# Audio_Amp.net
KiCad netlist of a schematic drawn in Altium Designer
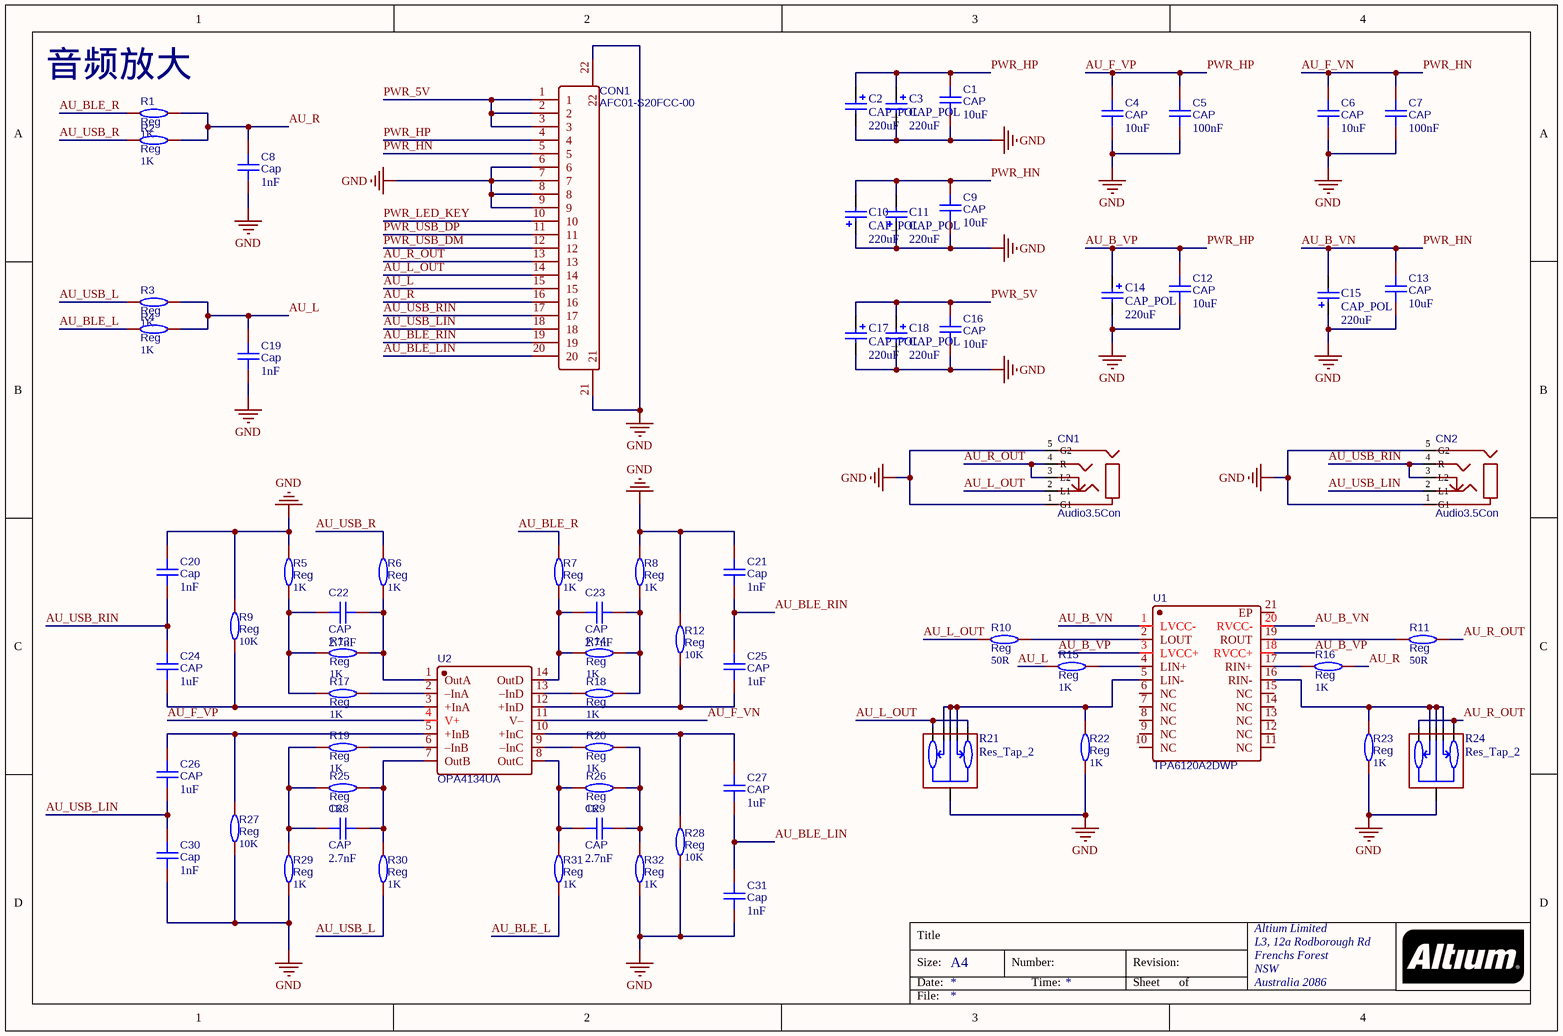
[diagram p0: Audio_Amp.SchDoc]

(export (version "E")
  (design (tool "Eeschema 10.0.6"))
  (components
    (comp (ref "C1")
      (value "CAP")
      (footprint "C0603")
      (description "Cap")
      (fields
        (field (name "BOM_SUPPLIER PART") "C302008")
        (field (name "BOM_MANUFACTURER PART") "0603B103K101CT")
        (field (name "ALTIUM_VALUE") "10uF")
        (field (name "CONTRIBUTOR") "LCSC")
      )
      (libsource (lib "Levent_lib") (part "CAP"))
    )
    (comp (ref "C2")
      (value "CAP_POL")
      (footprint "CAP_SMD_10mm")
      (description "极性电容")
      (fields (field (name "ALTIUM_VALUE") "220uF"))
      (libsource (lib "Levent_lib") (part "CAP_POL"))
    )
    (comp (ref "C3")
      (value "CAP_POL")
      (footprint "CAP_SMD_10mm")
      (description "极性电容")
      (fields (field (name "ALTIUM_VALUE") "220uF"))
      (libsource (lib "Levent_lib") (part "CAP_POL"))
    )
    (comp (ref "C4")
      (value "CAP")
      (footprint "C0603")
      (description "Cap")
      (fields
        (field (name "BOM_SUPPLIER PART") "C302008")
        (field (name "BOM_MANUFACTURER PART") "0603B103K101CT")
        (field (name "ALTIUM_VALUE") "10uF")
        (field (name "CONTRIBUTOR") "LCSC")
      )
      (libsource (lib "Levent_lib") (part "CAP"))
    )
    (comp (ref "C5")
      (value "CAP")
      (footprint "C0603")
      (description "Cap")
      (fields
        (field (name "BOM_SUPPLIER PART") "C302008")
        (field (name "BOM_MANUFACTURER PART") "0603B103K101CT")
        (field (name "ALTIUM_VALUE") "100nF")
        (field (name "CONTRIBUTOR") "LCSC")
      )
      (libsource (lib "Levent_lib") (part "CAP"))
    )
    (comp (ref "C6")
      (value "CAP")
      (footprint "C0603")
      (description "Cap")
      (fields
        (field (name "BOM_SUPPLIER PART") "C302008")
        (field (name "BOM_MANUFACTURER PART") "0603B103K101CT")
        (field (name "ALTIUM_VALUE") "10uF")
        (field (name "CONTRIBUTOR") "LCSC")
      )
      (libsource (lib "Levent_lib") (part "CAP"))
    )
    (comp (ref "C7")
      (value "CAP")
      (footprint "C0603")
      (description "Cap")
      (fields
        (field (name "BOM_SUPPLIER PART") "C302008")
        (field (name "BOM_MANUFACTURER PART") "0603B103K101CT")
        (field (name "ALTIUM_VALUE") "100nF")
        (field (name "CONTRIBUTOR") "LCSC")
      )
      (libsource (lib "Levent_lib") (part "CAP"))
    )
    (comp (ref "C8")
      (value "Cap")
      (footprint "C0603")
      (fields
        (field (name "BOM_SUPPLIER PART") "C302008")
        (field (name "BOM_MANUFACTURER PART") "0603B103K101CT")
        (field (name "ALTIUM_VALUE") "1nF")
        (field (name "CONTRIBUTOR") "LCSC")
      )
      (libsource (lib "Levent_lib") (part "CAP"))
    )
    (comp (ref "C9")
      (value "CAP")
      (footprint "C0603")
      (description "Cap")
      (fields
        (field (name "BOM_SUPPLIER PART") "C302008")
        (field (name "BOM_MANUFACTURER PART") "0603B103K101CT")
        (field (name "ALTIUM_VALUE") "10uF")
        (field (name "CONTRIBUTOR") "LCSC")
      )
      (libsource (lib "Levent_lib") (part "CAP"))
    )
    (comp (ref "C10")
      (value "CAP_POL")
      (footprint "CAP_SMD_10mm")
      (description "极性电容")
      (fields (field (name "ALTIUM_VALUE") "220uF"))
      (libsource (lib "Levent_lib") (part "CAP_POL"))
    )
    (comp (ref "C11")
      (value "CAP_POL")
      (footprint "CAP_SMD_10mm")
      (description "极性电容")
      (fields (field (name "ALTIUM_VALUE") "220uF"))
      (libsource (lib "Levent_lib") (part "CAP_POL"))
    )
    (comp (ref "C12")
      (value "CAP")
      (footprint "C0603")
      (description "Cap")
      (fields
        (field (name "BOM_SUPPLIER PART") "C302008")
        (field (name "BOM_MANUFACTURER PART") "0603B103K101CT")
        (field (name "ALTIUM_VALUE") "10uF")
        (field (name "CONTRIBUTOR") "LCSC")
      )
      (libsource (lib "Levent_lib") (part "CAP"))
    )
    (comp (ref "C13")
      (value "CAP")
      (footprint "C0603")
      (description "Cap")
      (fields
        (field (name "BOM_SUPPLIER PART") "C302008")
        (field (name "BOM_MANUFACTURER PART") "0603B103K101CT")
        (field (name "ALTIUM_VALUE") "10uF")
        (field (name "CONTRIBUTOR") "LCSC")
      )
      (libsource (lib "Levent_lib") (part "CAP"))
    )
    (comp (ref "C14")
      (value "CAP_POL")
      (footprint "CAP_SMD_10mm")
      (description "极性电容")
      (fields (field (name "ALTIUM_VALUE") "220uF"))
      (libsource (lib "Levent_lib") (part "CAP_POL"))
    )
    (comp (ref "C15")
      (value "CAP_POL")
      (footprint "CAP_SMD_10mm")
      (description "极性电容")
      (fields (field (name "ALTIUM_VALUE") "220uF"))
      (libsource (lib "Levent_lib") (part "CAP_POL"))
    )
    (comp (ref "C16")
      (value "CAP")
      (footprint "C0603")
      (description "Cap")
      (fields
        (field (name "BOM_SUPPLIER PART") "C302008")
        (field (name "BOM_MANUFACTURER PART") "0603B103K101CT")
        (field (name "ALTIUM_VALUE") "10uF")
        (field (name "CONTRIBUTOR") "LCSC")
      )
      (libsource (lib "Levent_lib") (part "CAP"))
    )
    (comp (ref "C17")
      (value "CAP_POL")
      (footprint "CAP_SMD_10mm")
      (description "极性电容")
      (fields (field (name "ALTIUM_VALUE") "220uF"))
      (libsource (lib "Levent_lib") (part "CAP_POL"))
    )
    (comp (ref "C18")
      (value "CAP_POL")
      (footprint "CAP_SMD_10mm")
      (description "极性电容")
      (fields (field (name "ALTIUM_VALUE") "220uF"))
      (libsource (lib "Levent_lib") (part "CAP_POL"))
    )
    (comp (ref "C19")
      (value "Cap")
      (footprint "C0603")
      (fields
        (field (name "BOM_SUPPLIER PART") "C302008")
        (field (name "BOM_MANUFACTURER PART") "0603B103K101CT")
        (field (name "ALTIUM_VALUE") "1nF")
        (field (name "CONTRIBUTOR") "LCSC")
      )
      (libsource (lib "Levent_lib") (part "CAP"))
    )
    (comp (ref "C20")
      (value "Cap")
      (footprint "C0603")
      (fields
        (field (name "BOM_SUPPLIER PART") "C302008")
        (field (name "BOM_MANUFACTURER PART") "0603B103K101CT")
        (field (name "ALTIUM_VALUE") "1nF")
        (field (name "CONTRIBUTOR") "LCSC")
      )
      (libsource (lib "Levent_lib") (part "CAP"))
    )
    (comp (ref "C21")
      (value "Cap")
      (footprint "C0603")
      (fields
        (field (name "BOM_SUPPLIER PART") "C302008")
        (field (name "BOM_MANUFACTURER PART") "0603B103K101CT")
        (field (name "ALTIUM_VALUE") "1nF")
        (field (name "CONTRIBUTOR") "LCSC")
      )
      (libsource (lib "Levent_lib") (part "CAP"))
    )
    (comp (ref "C22")
      (value "CAP")
      (footprint "C0603")
      (description "Cap")
      (fields
        (field (name "BOM_SUPPLIER PART") "C302008")
        (field (name "BOM_MANUFACTURER PART") "0603B103K101CT")
        (field (name "ALTIUM_VALUE") "2.7nF")
        (field (name "CONTRIBUTOR") "LCSC")
      )
      (libsource (lib "Levent_lib") (part "CAP"))
    )
    (comp (ref "C23")
      (value "CAP")
      (footprint "C0603")
      (description "Cap")
      (fields
        (field (name "BOM_SUPPLIER PART") "C302008")
        (field (name "BOM_MANUFACTURER PART") "0603B103K101CT")
        (field (name "ALTIUM_VALUE") "2.7nF")
        (field (name "CONTRIBUTOR") "LCSC")
      )
      (libsource (lib "Levent_lib") (part "CAP"))
    )
    (comp (ref "C24")
      (value "CAP")
      (footprint "C0603")
      (description "Cap")
      (fields
        (field (name "BOM_SUPPLIER PART") "C302008")
        (field (name "BOM_MANUFACTURER PART") "0603B103K101CT")
        (field (name "ALTIUM_VALUE") "1uF")
        (field (name "CONTRIBUTOR") "LCSC")
      )
      (libsource (lib "Levent_lib") (part "CAP"))
    )
    (comp (ref "C25")
      (value "CAP")
      (footprint "C0603")
      (description "Cap")
      (fields
        (field (name "BOM_SUPPLIER PART") "C302008")
        (field (name "BOM_MANUFACTURER PART") "0603B103K101CT")
        (field (name "ALTIUM_VALUE") "1uF")
        (field (name "CONTRIBUTOR") "LCSC")
      )
      (libsource (lib "Levent_lib") (part "CAP"))
    )
    (comp (ref "C26")
      (value "CAP")
      (footprint "C0603")
      (description "Cap")
      (fields
        (field (name "BOM_SUPPLIER PART") "C302008")
        (field (name "BOM_MANUFACTURER PART") "0603B103K101CT")
        (field (name "ALTIUM_VALUE") "1uF")
        (field (name "CONTRIBUTOR") "LCSC")
      )
      (libsource (lib "Levent_lib") (part "CAP"))
    )
    (comp (ref "C27")
      (value "CAP")
      (footprint "C0603")
      (description "Cap")
      (fields
        (field (name "BOM_SUPPLIER PART") "C302008")
        (field (name "BOM_MANUFACTURER PART") "0603B103K101CT")
        (field (name "ALTIUM_VALUE") "1uF")
        (field (name "CONTRIBUTOR") "LCSC")
      )
      (libsource (lib "Levent_lib") (part "CAP"))
    )
    (comp (ref "C28")
      (value "CAP")
      (footprint "C0603")
      (description "Cap")
      (fields
        (field (name "BOM_SUPPLIER PART") "C302008")
        (field (name "BOM_MANUFACTURER PART") "0603B103K101CT")
        (field (name "ALTIUM_VALUE") "2.7nF")
        (field (name "CONTRIBUTOR") "LCSC")
      )
      (libsource (lib "Levent_lib") (part "CAP"))
    )
    (comp (ref "C29")
      (value "CAP")
      (footprint "C0603")
      (description "Cap")
      (fields
        (field (name "BOM_SUPPLIER PART") "C302008")
        (field (name "BOM_MANUFACTURER PART") "0603B103K101CT")
        (field (name "ALTIUM_VALUE") "2.7nF")
        (field (name "CONTRIBUTOR") "LCSC")
      )
      (libsource (lib "Levent_lib") (part "CAP"))
    )
    (comp (ref "C30")
      (value "Cap")
      (footprint "C0603")
      (fields
        (field (name "BOM_SUPPLIER PART") "C302008")
        (field (name "BOM_MANUFACTURER PART") "0603B103K101CT")
        (field (name "ALTIUM_VALUE") "1nF")
        (field (name "CONTRIBUTOR") "LCSC")
      )
      (libsource (lib "Levent_lib") (part "CAP"))
    )
    (comp (ref "C31")
      (value "Cap")
      (footprint "C0603")
      (fields
        (field (name "BOM_SUPPLIER PART") "C302008")
        (field (name "BOM_MANUFACTURER PART") "0603B103K101CT")
        (field (name "ALTIUM_VALUE") "1nF")
        (field (name "CONTRIBUTOR") "LCSC")
      )
      (libsource (lib "Levent_lib") (part "CAP"))
    )
    (comp (ref "CN1")
      (value "Audio3.5Con")
      (footprint "Audio3.5_3Pin")
      (description "3.5mm 3Pin 音频接口")
      (fields
        (field (name "BOM_SUPPLIER PART") "C2837065")
        (field (name "BOM_MANUFACTURER PART") "PJ-393")
        (field (name "CONTRIBUTOR") "LCSC")
      )
      (libsource (lib "Levent_lib") (part "AudioCon3"))
    )
    (comp (ref "CN2")
      (value "Audio3.5Con")
      (footprint "Audio3.5_3Pin")
      (description "3.5mm 3Pin 音频接口")
      (fields
        (field (name "BOM_SUPPLIER PART") "C2837065")
        (field (name "BOM_MANUFACTURER PART") "PJ-393")
        (field (name "CONTRIBUTOR") "LCSC")
      )
      (libsource (lib "Levent_lib") (part "AudioCon3"))
    )
    (comp (ref "CON1")
      (value "AFC01-S20FCC-00")
      (footprint "FPC-SMD_20P_0.5")
      (description "FPC连接器20Pin")
      (fields (field (name "BOM_SUPPLIER PART") "C262274") (field (name "CONTRIBUTOR") "LCSC"))
      (libsource (lib "Levent_lib") (part "FPC_CONN_20"))
    )
    (comp (ref "R1")
      (value "Reg")
      (footprint "R0603")
      (description "电阻")
      (fields
        (field (name "BOM_SUPPLIER PART") "C465721")
        (field (name "BOM_MANUFACTURER PART") "AR03BTCX1002A")
        (field (name "ALTIUM_VALUE") "1K")
        (field (name "CONTRIBUTOR") "LCSC")
      )
      (libsource (lib "Levent_lib") (part "Res"))
    )
    (comp (ref "R2")
      (value "Reg")
      (footprint "R0603")
      (description "电阻")
      (fields
        (field (name "BOM_SUPPLIER PART") "C465721")
        (field (name "BOM_MANUFACTURER PART") "AR03BTCX1002A")
        (field (name "ALTIUM_VALUE") "1K")
        (field (name "CONTRIBUTOR") "LCSC")
      )
      (libsource (lib "Levent_lib") (part "Res"))
    )
    (comp (ref "R3")
      (value "Reg")
      (footprint "R0603")
      (description "电阻")
      (fields
        (field (name "BOM_SUPPLIER PART") "C465721")
        (field (name "BOM_MANUFACTURER PART") "AR03BTCX1002A")
        (field (name "ALTIUM_VALUE") "1K")
        (field (name "CONTRIBUTOR") "LCSC")
      )
      (libsource (lib "Levent_lib") (part "Res"))
    )
    (comp (ref "R4")
      (value "Reg")
      (footprint "R0603")
      (description "电阻")
      (fields
        (field (name "BOM_SUPPLIER PART") "C465721")
        (field (name "BOM_MANUFACTURER PART") "AR03BTCX1002A")
        (field (name "ALTIUM_VALUE") "1K")
        (field (name "CONTRIBUTOR") "LCSC")
      )
      (libsource (lib "Levent_lib") (part "Res"))
    )
    (comp (ref "R5")
      (value "Reg")
      (footprint "R0603")
      (description "电阻")
      (fields
        (field (name "BOM_SUPPLIER PART") "C465721")
        (field (name "BOM_MANUFACTURER PART") "AR03BTCX1002A")
        (field (name "ALTIUM_VALUE") "1K")
        (field (name "CONTRIBUTOR") "LCSC")
      )
      (libsource (lib "Levent_lib") (part "Res"))
    )
    (comp (ref "R6")
      (value "Reg")
      (footprint "R0603")
      (description "电阻")
      (fields
        (field (name "BOM_SUPPLIER PART") "C465721")
        (field (name "BOM_MANUFACTURER PART") "AR03BTCX1002A")
        (field (name "ALTIUM_VALUE") "1K")
        (field (name "CONTRIBUTOR") "LCSC")
      )
      (libsource (lib "Levent_lib") (part "Res"))
    )
    (comp (ref "R7")
      (value "Reg")
      (footprint "R0603")
      (description "电阻")
      (fields
        (field (name "BOM_SUPPLIER PART") "C465721")
        (field (name "BOM_MANUFACTURER PART") "AR03BTCX1002A")
        (field (name "ALTIUM_VALUE") "1K")
        (field (name "CONTRIBUTOR") "LCSC")
      )
      (libsource (lib "Levent_lib") (part "Res"))
    )
    (comp (ref "R8")
      (value "Reg")
      (footprint "R0603")
      (description "电阻")
      (fields
        (field (name "BOM_SUPPLIER PART") "C465721")
        (field (name "BOM_MANUFACTURER PART") "AR03BTCX1002A")
        (field (name "ALTIUM_VALUE") "1K")
        (field (name "CONTRIBUTOR") "LCSC")
      )
      (libsource (lib "Levent_lib") (part "Res"))
    )
    (comp (ref "R9")
      (value "Reg")
      (footprint "R0603")
      (description "电阻")
      (fields
        (field (name "BOM_SUPPLIER PART") "C465721")
        (field (name "BOM_MANUFACTURER PART") "AR03BTCX1002A")
        (field (name "ALTIUM_VALUE") "10K")
        (field (name "CONTRIBUTOR") "LCSC")
      )
      (libsource (lib "Levent_lib") (part "Res"))
    )
    (comp (ref "R10")
      (value "Reg")
      (footprint "R0603")
      (description "电阻")
      (fields
        (field (name "BOM_SUPPLIER PART") "C465721")
        (field (name "BOM_MANUFACTURER PART") "AR03BTCX1002A")
        (field (name "ALTIUM_VALUE") "50R")
        (field (name "CONTRIBUTOR") "LCSC")
      )
      (libsource (lib "Levent_lib") (part "Res"))
    )
    (comp (ref "R11")
      (value "Reg")
      (footprint "R0603")
      (description "电阻")
      (fields
        (field (name "BOM_SUPPLIER PART") "C465721")
        (field (name "BOM_MANUFACTURER PART") "AR03BTCX1002A")
        (field (name "ALTIUM_VALUE") "50R")
        (field (name "CONTRIBUTOR") "LCSC")
      )
      (libsource (lib "Levent_lib") (part "Res"))
    )
    (comp (ref "R12")
      (value "Reg")
      (footprint "R0603")
      (description "电阻")
      (fields
        (field (name "BOM_SUPPLIER PART") "C465721")
        (field (name "BOM_MANUFACTURER PART") "AR03BTCX1002A")
        (field (name "ALTIUM_VALUE") "10K")
        (field (name "CONTRIBUTOR") "LCSC")
      )
      (libsource (lib "Levent_lib") (part "Res"))
    )
    (comp (ref "R13")
      (value "Reg")
      (footprint "R0603")
      (description "电阻")
      (fields
        (field (name "BOM_SUPPLIER PART") "C465721")
        (field (name "BOM_MANUFACTURER PART") "AR03BTCX1002A")
        (field (name "ALTIUM_VALUE") "1K")
        (field (name "CONTRIBUTOR") "LCSC")
      )
      (libsource (lib "Levent_lib") (part "Res"))
    )
    (comp (ref "R14")
      (value "Reg")
      (footprint "R0603")
      (description "电阻")
      (fields
        (field (name "BOM_SUPPLIER PART") "C465721")
        (field (name "BOM_MANUFACTURER PART") "AR03BTCX1002A")
        (field (name "ALTIUM_VALUE") "1K")
        (field (name "CONTRIBUTOR") "LCSC")
      )
      (libsource (lib "Levent_lib") (part "Res"))
    )
    (comp (ref "R15")
      (value "Reg")
      (footprint "R0603")
      (description "电阻")
      (fields
        (field (name "BOM_SUPPLIER PART") "C465721")
        (field (name "BOM_MANUFACTURER PART") "AR03BTCX1002A")
        (field (name "ALTIUM_VALUE") "1K")
        (field (name "CONTRIBUTOR") "LCSC")
      )
      (libsource (lib "Levent_lib") (part "Res"))
    )
    (comp (ref "R16")
      (value "Reg")
      (footprint "R0603")
      (description "电阻")
      (fields
        (field (name "BOM_SUPPLIER PART") "C465721")
        (field (name "BOM_MANUFACTURER PART") "AR03BTCX1002A")
        (field (name "ALTIUM_VALUE") "1K")
        (field (name "CONTRIBUTOR") "LCSC")
      )
      (libsource (lib "Levent_lib") (part "Res"))
    )
    (comp (ref "R17")
      (value "Reg")
      (footprint "R0603")
      (description "电阻")
      (fields
        (field (name "BOM_SUPPLIER PART") "C465721")
        (field (name "BOM_MANUFACTURER PART") "AR03BTCX1002A")
        (field (name "ALTIUM_VALUE") "1K")
        (field (name "CONTRIBUTOR") "LCSC")
      )
      (libsource (lib "Levent_lib") (part "Res"))
    )
    (comp (ref "R18")
      (value "Reg")
      (footprint "R0603")
      (description "电阻")
      (fields
        (field (name "BOM_SUPPLIER PART") "C465721")
        (field (name "BOM_MANUFACTURER PART") "AR03BTCX1002A")
        (field (name "ALTIUM_VALUE") "1K")
        (field (name "CONTRIBUTOR") "LCSC")
      )
      (libsource (lib "Levent_lib") (part "Res"))
    )
    (comp (ref "R19")
      (value "Reg")
      (footprint "R0603")
      (description "电阻")
      (fields
        (field (name "BOM_SUPPLIER PART") "C465721")
        (field (name "BOM_MANUFACTURER PART") "AR03BTCX1002A")
        (field (name "ALTIUM_VALUE") "1K")
        (field (name "CONTRIBUTOR") "LCSC")
      )
      (libsource (lib "Levent_lib") (part "Res"))
    )
    (comp (ref "R20")
      (value "Reg")
      (footprint "R0603")
      (description "电阻")
      (fields
        (field (name "BOM_SUPPLIER PART") "C465721")
        (field (name "BOM_MANUFACTURER PART") "AR03BTCX1002A")
        (field (name "ALTIUM_VALUE") "1K")
        (field (name "CONTRIBUTOR") "LCSC")
      )
      (libsource (lib "Levent_lib") (part "Res"))
    )
    (comp (ref "R21")
      (value "Res_Tap_2")
      (footprint "RES_TAP_5Pin")
      (description "双联电位器")
      (libsource (lib "Levent_lib") (part "Res_Tap_2"))
    )
    (comp (ref "R22")
      (value "Reg")
      (footprint "R0603")
      (description "电阻")
      (fields
        (field (name "BOM_SUPPLIER PART") "C465721")
        (field (name "BOM_MANUFACTURER PART") "AR03BTCX1002A")
        (field (name "ALTIUM_VALUE") "1K")
        (field (name "CONTRIBUTOR") "LCSC")
      )
      (libsource (lib "Levent_lib") (part "Res"))
    )
    (comp (ref "R23")
      (value "Reg")
      (footprint "R0603")
      (description "电阻")
      (fields
        (field (name "BOM_SUPPLIER PART") "C465721")
        (field (name "BOM_MANUFACTURER PART") "AR03BTCX1002A")
        (field (name "ALTIUM_VALUE") "1K")
        (field (name "CONTRIBUTOR") "LCSC")
      )
      (libsource (lib "Levent_lib") (part "Res"))
    )
    (comp (ref "R24")
      (value "Res_Tap_2")
      (footprint "RES_TAP_5Pin")
      (description "双联电位器")
      (libsource (lib "Levent_lib") (part "Res_Tap_2"))
    )
    (comp (ref "R25")
      (value "Reg")
      (footprint "R0603")
      (description "电阻")
      (fields
        (field (name "BOM_SUPPLIER PART") "C465721")
        (field (name "BOM_MANUFACTURER PART") "AR03BTCX1002A")
        (field (name "ALTIUM_VALUE") "1K")
        (field (name "CONTRIBUTOR") "LCSC")
      )
      (libsource (lib "Levent_lib") (part "Res"))
    )
    (comp (ref "R26")
      (value "Reg")
      (footprint "R0603")
      (description "电阻")
      (fields
        (field (name "BOM_SUPPLIER PART") "C465721")
        (field (name "BOM_MANUFACTURER PART") "AR03BTCX1002A")
        (field (name "ALTIUM_VALUE") "1K")
        (field (name "CONTRIBUTOR") "LCSC")
      )
      (libsource (lib "Levent_lib") (part "Res"))
    )
    (comp (ref "R27")
      (value "Reg")
      (footprint "R0603")
      (description "电阻")
      (fields
        (field (name "BOM_SUPPLIER PART") "C465721")
        (field (name "BOM_MANUFACTURER PART") "AR03BTCX1002A")
        (field (name "ALTIUM_VALUE") "10K")
        (field (name "CONTRIBUTOR") "LCSC")
      )
      (libsource (lib "Levent_lib") (part "Res"))
    )
    (comp (ref "R28")
      (value "Reg")
      (footprint "R0603")
      (description "电阻")
      (fields
        (field (name "BOM_SUPPLIER PART") "C465721")
        (field (name "BOM_MANUFACTURER PART") "AR03BTCX1002A")
        (field (name "ALTIUM_VALUE") "10K")
        (field (name "CONTRIBUTOR") "LCSC")
      )
      (libsource (lib "Levent_lib") (part "Res"))
    )
    (comp (ref "R29")
      (value "Reg")
      (footprint "R0603")
      (description "电阻")
      (fields
        (field (name "BOM_SUPPLIER PART") "C465721")
        (field (name "BOM_MANUFACTURER PART") "AR03BTCX1002A")
        (field (name "ALTIUM_VALUE") "1K")
        (field (name "CONTRIBUTOR") "LCSC")
      )
      (libsource (lib "Levent_lib") (part "Res"))
    )
    (comp (ref "R30")
      (value "Reg")
      (footprint "R0603")
      (description "电阻")
      (fields
        (field (name "BOM_SUPPLIER PART") "C465721")
        (field (name "BOM_MANUFACTURER PART") "AR03BTCX1002A")
        (field (name "ALTIUM_VALUE") "1K")
        (field (name "CONTRIBUTOR") "LCSC")
      )
      (libsource (lib "Levent_lib") (part "Res"))
    )
    (comp (ref "R31")
      (value "Reg")
      (footprint "R0603")
      (description "电阻")
      (fields
        (field (name "BOM_SUPPLIER PART") "C465721")
        (field (name "BOM_MANUFACTURER PART") "AR03BTCX1002A")
        (field (name "ALTIUM_VALUE") "1K")
        (field (name "CONTRIBUTOR") "LCSC")
      )
      (libsource (lib "Levent_lib") (part "Res"))
    )
    (comp (ref "R32")
      (value "Reg")
      (footprint "R0603")
      (description "电阻")
      (fields
        (field (name "BOM_SUPPLIER PART") "C465721")
        (field (name "BOM_MANUFACTURER PART") "AR03BTCX1002A")
        (field (name "ALTIUM_VALUE") "1K")
        (field (name "CONTRIBUTOR") "LCSC")
      )
      (libsource (lib "Levent_lib") (part "Res"))
    )
    (comp (ref "U1")
      (value "TPA6120A2DWP")
      (footprint "HSOP-20_L12.8-W7.5-P1.27-LS10.3-BL-EP")
      (description "耳放")
      (fields (field (name "BOM_SUPPLIER PART") "C2871054") (field (name "CONTRIBUTOR") "LCSC"))
      (libsource (lib "Levent_lib") (part "TPA6120"))
    )
    (comp (ref "U2")
      (value "OPA4134UA")
      (footprint "SOIC-14_L8.7-W3.9-P1.27-LS6.0-BL")
      (description "耳放")
      (fields (field (name "BOM_SUPPLIER PART") "C2832240") (field (name "CONTRIBUTOR") "LCSC"))
      (libsource (lib "Levent_lib") (part "OPA4134UA"))
    )
  )
  (nets
    (net (code "1") (name "/AU_BLE_L") (class "Default")
      (node (ref "R31") (pin "1") (pinfunction "1_1") (pintype "passive"))
      (node (ref "R4") (pin "2") (pinfunction "2_2") (pintype "passive"))
    )
    (net (code "2") (name "/AU_BLE_LIN") (class "Default")
      (node (ref "C27") (pin "1") (pinfunction "1_1") (pintype "passive"))
      (node (ref "C31") (pin "2") (pinfunction "2_2") (pintype "passive"))
      (node (ref "CON1") (pin "20") (pinfunction "20_20") (pintype "passive"))
    )
    (net (code "3") (name "/AU_BLE_R") (class "Default")
      (node (ref "R1") (pin "2") (pinfunction "2_2") (pintype "passive"))
      (node (ref "R7") (pin "2") (pinfunction "2_2") (pintype "passive"))
    )
    (net (code "4") (name "/AU_BLE_RIN") (class "Default")
      (node (ref "C21") (pin "1") (pinfunction "1_1") (pintype "passive"))
      (node (ref "C25") (pin "2") (pinfunction "2_2") (pintype "passive"))
      (node (ref "CON1") (pin "19") (pinfunction "19_19") (pintype "passive"))
    )
    (net (code "5") (name "/AU_B_VN") (class "Default")
      (node (ref "C10") (pin "2") (pinfunction "2_2") (pintype "passive"))
      (node (ref "C11") (pin "2") (pinfunction "2_2") (pintype "passive"))
      (node (ref "C13") (pin "2") (pinfunction "2_2") (pintype "passive"))
      (node (ref "C15") (pin "2") (pinfunction "2_2") (pintype "passive"))
      (node (ref "C6") (pin "2") (pinfunction "2_2") (pintype "passive"))
      (node (ref "C7") (pin "2") (pinfunction "2_2") (pintype "passive"))
      (node (ref "C9") (pin "2") (pinfunction "2_2") (pintype "passive"))
      (node (ref "CON1") (pin "5") (pinfunction "5_5") (pintype "passive"))
      (node (ref "U1") (pin "1") (pinfunction "LVCC-_1") (pintype "passive"))
      (node (ref "U1") (pin "20") (pinfunction "RVCC-_20") (pintype "passive"))
      (node (ref "U2") (pin "11") (pinfunction "V–_11") (pintype "passive"))
    )
    (net (code "6") (name "/AU_B_VP") (class "Default")
      (node (ref "C1") (pin "2") (pinfunction "2_2") (pintype "passive"))
      (node (ref "C12") (pin "2") (pinfunction "2_2") (pintype "passive"))
      (node (ref "C14") (pin "1") (pinfunction "1_1") (pintype "passive"))
      (node (ref "C2") (pin "1") (pinfunction "1_1") (pintype "passive"))
      (node (ref "C3") (pin "1") (pinfunction "1_1") (pintype "passive"))
      (node (ref "C4") (pin "2") (pinfunction "2_2") (pintype "passive"))
      (node (ref "C5") (pin "2") (pinfunction "2_2") (pintype "passive"))
      (node (ref "CON1") (pin "4") (pinfunction "4_4") (pintype "passive"))
      (node (ref "U1") (pin "18") (pinfunction "RVCC+_18") (pintype "passive"))
      (node (ref "U1") (pin "3") (pinfunction "LVCC+_3") (pintype "passive"))
      (node (ref "U2") (pin "4") (pinfunction "V+_4") (pintype "passive"))
    )
    (net (code "7") (name "/AU_L") (class "Default")
      (node (ref "C19") (pin "2") (pinfunction "2_2") (pintype "passive"))
      (node (ref "CON1") (pin "15") (pinfunction "15_15") (pintype "passive"))
      (node (ref "R15") (pin "1") (pinfunction "1_1") (pintype "passive"))
      (node (ref "R3") (pin "1") (pinfunction "1_1") (pintype "passive"))
      (node (ref "R4") (pin "1") (pinfunction "1_1") (pintype "passive"))
    )
    (net (code "8") (name "/AU_L_OUT") (class "Default")
      (node (ref "CN1") (pin "2") (pinfunction "L1_2") (pintype "passive"))
      (node (ref "CON1") (pin "14") (pinfunction "14_14") (pintype "passive"))
      (node (ref "R10") (pin "1") (pinfunction "1_1") (pintype "passive"))
      (node (ref "R21") (pin "4") (pinfunction "CH2B_4") (pintype "passive"))
      (node (ref "R21") (pin "5") (pinfunction "CH1B_5") (pintype "passive"))
    )
    (net (code "9") (name "/AU_R") (class "Default")
      (node (ref "C8") (pin "2") (pinfunction "2_2") (pintype "passive"))
      (node (ref "CON1") (pin "16") (pinfunction "16_16") (pintype "passive"))
      (node (ref "R1") (pin "1") (pinfunction "1_1") (pintype "passive"))
      (node (ref "R16") (pin "2") (pinfunction "2_2") (pintype "passive"))
      (node (ref "R2") (pin "1") (pinfunction "1_1") (pintype "passive"))
    )
    (net (code "10") (name "/AU_R_OUT") (class "Default")
      (node (ref "CN1") (pin "3") (pinfunction "L2_3") (pintype "passive"))
      (node (ref "CN1") (pin "4") (pinfunction "R_4") (pintype "passive"))
      (node (ref "CON1") (pin "13") (pinfunction "13_13") (pintype "passive"))
      (node (ref "R11") (pin "2") (pinfunction "2_2") (pintype "passive"))
      (node (ref "R24") (pin "4") (pinfunction "CH2B_4") (pintype "passive"))
      (node (ref "R24") (pin "5") (pinfunction "CH1B_5") (pintype "passive"))
    )
    (net (code "11") (name "/AU_USB_L") (class "Default")
      (node (ref "R3") (pin "2") (pinfunction "2_2") (pintype "passive"))
      (node (ref "R30") (pin "1") (pinfunction "1_1") (pintype "passive"))
    )
    (net (code "12") (name "/AU_USB_LIN") (class "Default")
      (node (ref "C26") (pin "2") (pinfunction "2_2") (pintype "passive"))
      (node (ref "C30") (pin "1") (pinfunction "1_1") (pintype "passive"))
      (node (ref "CN2") (pin "2") (pinfunction "L1_2") (pintype "passive"))
      (node (ref "CON1") (pin "18") (pinfunction "18_18") (pintype "passive"))
    )
    (net (code "13") (name "/AU_USB_R") (class "Default")
      (node (ref "R2") (pin "2") (pinfunction "2_2") (pintype "passive"))
      (node (ref "R6") (pin "2") (pinfunction "2_2") (pintype "passive"))
    )
    (net (code "14") (name "/AU_USB_RIN") (class "Default")
      (node (ref "C20") (pin "1") (pinfunction "1_1") (pintype "passive"))
      (node (ref "C24") (pin "1") (pinfunction "1_1") (pintype "passive"))
      (node (ref "CN2") (pin "3") (pinfunction "L2_3") (pintype "passive"))
      (node (ref "CN2") (pin "4") (pinfunction "R_4") (pintype "passive"))
      (node (ref "CON1") (pin "17") (pinfunction "17_17") (pintype "passive"))
    )
    (net (code "15") (name "/PWR_5V") (class "Default")
      (node (ref "C16") (pin "2") (pinfunction "2_2") (pintype "passive"))
      (node (ref "C17") (pin "1") (pinfunction "1_1") (pintype "passive"))
      (node (ref "C18") (pin "1") (pinfunction "1_1") (pintype "passive"))
      (node (ref "CON1") (pin "1") (pinfunction "1_1") (pintype "passive"))
      (node (ref "CON1") (pin "2") (pinfunction "2_2") (pintype "passive"))
      (node (ref "CON1") (pin "3") (pinfunction "3_3") (pintype "passive"))
    )
    (net (code "16") (name "/PWR_LED_KEY") (class "Default")
      (node (ref "CON1") (pin "10") (pinfunction "10_10") (pintype "passive"))
    )
    (net (code "17") (name "/PWR_USB_DM") (class "Default")
      (node (ref "CON1") (pin "12") (pinfunction "12_12") (pintype "passive"))
    )
    (net (code "18") (name "/PWR_USB_DP") (class "Default")
      (node (ref "CON1") (pin "11") (pinfunction "11_11") (pintype "passive"))
    )
    (net (code "19") (name "GND") (class "Default")
      (node (ref "C1") (pin "1") (pinfunction "1_1") (pintype "passive"))
      (node (ref "C10") (pin "1") (pinfunction "1_1") (pintype "passive"))
      (node (ref "C11") (pin "1") (pinfunction "1_1") (pintype "passive"))
      (node (ref "C12") (pin "1") (pinfunction "1_1") (pintype "passive"))
      (node (ref "C13") (pin "1") (pinfunction "1_1") (pintype "passive"))
      (node (ref "C14") (pin "2") (pinfunction "2_2") (pintype "passive"))
      (node (ref "C15") (pin "1") (pinfunction "1_1") (pintype "passive"))
      (node (ref "C16") (pin "1") (pinfunction "1_1") (pintype "passive"))
      (node (ref "C17") (pin "2") (pinfunction "2_2") (pintype "passive"))
      (node (ref "C18") (pin "2") (pinfunction "2_2") (pintype "passive"))
      (node (ref "C19") (pin "1") (pinfunction "1_1") (pintype "passive"))
      (node (ref "C2") (pin "2") (pinfunction "2_2") (pintype "passive"))
      (node (ref "C20") (pin "2") (pinfunction "2_2") (pintype "passive"))
      (node (ref "C21") (pin "2") (pinfunction "2_2") (pintype "passive"))
      (node (ref "C3") (pin "2") (pinfunction "2_2") (pintype "passive"))
      (node (ref "C30") (pin "2") (pinfunction "2_2") (pintype "passive"))
      (node (ref "C31") (pin "1") (pinfunction "1_1") (pintype "passive"))
      (node (ref "C4") (pin "1") (pinfunction "1_1") (pintype "passive"))
      (node (ref "C5") (pin "1") (pinfunction "1_1") (pintype "passive"))
      (node (ref "C6") (pin "1") (pinfunction "1_1") (pintype "passive"))
      (node (ref "C7") (pin "1") (pinfunction "1_1") (pintype "passive"))
      (node (ref "C8") (pin "1") (pinfunction "1_1") (pintype "passive"))
      (node (ref "C9") (pin "1") (pinfunction "1_1") (pintype "passive"))
      (node (ref "CN1") (pin "1") (pinfunction "G1_1") (pintype "passive"))
      (node (ref "CN1") (pin "5") (pinfunction "G2_5") (pintype "passive"))
      (node (ref "CN2") (pin "1") (pinfunction "G1_1") (pintype "passive"))
      (node (ref "CN2") (pin "5") (pinfunction "G2_5") (pintype "passive"))
      (node (ref "CON1") (pin "21") (pinfunction "21_21") (pintype "passive"))
      (node (ref "CON1") (pin "22") (pinfunction "22_22") (pintype "passive"))
      (node (ref "CON1") (pin "6") (pinfunction "6_6") (pintype "passive"))
      (node (ref "CON1") (pin "7") (pinfunction "7_7") (pintype "passive"))
      (node (ref "CON1") (pin "8") (pinfunction "8_8") (pintype "passive"))
      (node (ref "CON1") (pin "9") (pinfunction "9_9") (pintype "passive"))
      (node (ref "R12") (pin "1") (pinfunction "1_1") (pintype "passive"))
      (node (ref "R21") (pin "6") (pinfunction "PAD_6") (pintype "passive"))
      (node (ref "R22") (pin "1") (pinfunction "1_1") (pintype "passive"))
      (node (ref "R23") (pin "1") (pinfunction "1_1") (pintype "passive"))
      (node (ref "R24") (pin "6") (pinfunction "PAD_6") (pintype "passive"))
      (node (ref "R27") (pin "2") (pinfunction "2_2") (pintype "passive"))
      (node (ref "R28") (pin "2") (pinfunction "2_2") (pintype "passive"))
      (node (ref "R29") (pin "1") (pinfunction "1_1") (pintype "passive"))
      (node (ref "R32") (pin "1") (pinfunction "1_1") (pintype "passive"))
      (node (ref "R5") (pin "2") (pinfunction "2_2") (pintype "passive"))
      (node (ref "R8") (pin "2") (pinfunction "2_2") (pintype "passive"))
      (node (ref "R9") (pin "1") (pinfunction "1_1") (pintype "passive"))
    )
    (net (code "20") (name "Net-(C22-Pad1)") (class "Default")
      (node (ref "C22") (pin "1") (pinfunction "1_1") (pintype "passive"))
      (node (ref "R13") (pin "2") (pinfunction "2_2") (pintype "passive"))
      (node (ref "R17") (pin "2") (pinfunction "2_2") (pintype "passive"))
      (node (ref "R5") (pin "1") (pinfunction "1_1") (pintype "passive"))
    )
    (net (code "21") (name "Net-(C23-Pad2)") (class "Default")
      (node (ref "C23") (pin "2") (pinfunction "2_2") (pintype "passive"))
      (node (ref "R14") (pin "1") (pinfunction "1_1") (pintype "passive"))
      (node (ref "R18") (pin "1") (pinfunction "1_1") (pintype "passive"))
      (node (ref "R8") (pin "1") (pinfunction "1_1") (pintype "passive"))
    )
    (net (code "22") (name "Net-(C28-Pad1)") (class "Default")
      (node (ref "C28") (pin "1") (pinfunction "1_1") (pintype "passive"))
      (node (ref "R19") (pin "2") (pinfunction "2_2") (pintype "passive"))
      (node (ref "R25") (pin "2") (pinfunction "2_2") (pintype "passive"))
      (node (ref "R29") (pin "2") (pinfunction "2_2") (pintype "passive"))
    )
    (net (code "23") (name "Net-(C29-Pad2)") (class "Default")
      (node (ref "C29") (pin "2") (pinfunction "2_2") (pintype "passive"))
      (node (ref "R20") (pin "1") (pinfunction "1_1") (pintype "passive"))
      (node (ref "R26") (pin "1") (pinfunction "1_1") (pintype "passive"))
      (node (ref "R32") (pin "2") (pinfunction "2_2") (pintype "passive"))
    )
    (net (code "24") (name "Net-(R21-CH1A)") (class "Default")
      (node (ref "R21") (pin "1") (pinfunction "G_1") (pintype "passive"))
      (node (ref "R21") (pin "2") (pinfunction "CH1A_2") (pintype "passive"))
      (node (ref "R21") (pin "3") (pinfunction "CH2A_3") (pintype "passive"))
      (node (ref "R22") (pin "2") (pinfunction "2_2") (pintype "passive"))
      (node (ref "U1") (pin "5") (pinfunction "LIN-_5") (pintype "passive"))
    )
    (net (code "25") (name "Net-(R24-CH1A)") (class "Default")
      (node (ref "R23") (pin "2") (pinfunction "2_2") (pintype "passive"))
      (node (ref "R24") (pin "1") (pinfunction "G_1") (pintype "passive"))
      (node (ref "R24") (pin "2") (pinfunction "CH1A_2") (pintype "passive"))
      (node (ref "R24") (pin "3") (pinfunction "CH2A_3") (pintype "passive"))
      (node (ref "U1") (pin "16") (pinfunction "RIN-_16") (pintype "passive"))
    )
    (net (code "26") (name "Net-(U1-LIN+)") (class "Default")
      (node (ref "R15") (pin "2") (pinfunction "2_2") (pintype "passive"))
      (node (ref "U1") (pin "4") (pinfunction "LIN+_4") (pintype "passive"))
    )
    (net (code "27") (name "Net-(U1-LOUT)") (class "Default")
      (node (ref "R10") (pin "2") (pinfunction "2_2") (pintype "passive"))
      (node (ref "U1") (pin "2") (pinfunction "LOUT_2") (pintype "passive"))
    )
    (net (code "28") (name "Net-(U1-RIN+)") (class "Default")
      (node (ref "R16") (pin "1") (pinfunction "1_1") (pintype "passive"))
      (node (ref "U1") (pin "17") (pinfunction "RIN+_17") (pintype "passive"))
    )
    (net (code "29") (name "Net-(U1-ROUT)") (class "Default")
      (node (ref "R11") (pin "1") (pinfunction "1_1") (pintype "passive"))
      (node (ref "U1") (pin "19") (pinfunction "ROUT_19") (pintype "passive"))
    )
    (net (code "30") (name "Net-(U2-+InA)") (class "Default")
      (node (ref "C24") (pin "2") (pinfunction "2_2") (pintype "passive"))
      (node (ref "R9") (pin "2") (pinfunction "2_2") (pintype "passive"))
      (node (ref "U2") (pin "3") (pinfunction "+InA_3") (pintype "passive"))
    )
    (net (code "31") (name "Net-(U2-+InB)") (class "Default")
      (node (ref "C26") (pin "1") (pinfunction "1_1") (pintype "passive"))
      (node (ref "R27") (pin "1") (pinfunction "1_1") (pintype "passive"))
      (node (ref "U2") (pin "5") (pinfunction "+InB_5") (pintype "passive"))
    )
    (net (code "32") (name "Net-(U2-+InC)") (class "Default")
      (node (ref "C27") (pin "2") (pinfunction "2_2") (pintype "passive"))
      (node (ref "R28") (pin "1") (pinfunction "1_1") (pintype "passive"))
      (node (ref "U2") (pin "10") (pinfunction "+InC_10") (pintype "passive"))
    )
    (net (code "33") (name "Net-(U2-+InD)") (class "Default")
      (node (ref "C25") (pin "1") (pinfunction "1_1") (pintype "passive"))
      (node (ref "R12") (pin "2") (pinfunction "2_2") (pintype "passive"))
      (node (ref "U2") (pin "12") (pinfunction "+InD_12") (pintype "passive"))
    )
    (net (code "34") (name "Net-(U2-OutA)") (class "Default")
      (node (ref "C22") (pin "2") (pinfunction "2_2") (pintype "passive"))
      (node (ref "R13") (pin "1") (pinfunction "1_1") (pintype "passive"))
      (node (ref "R6") (pin "1") (pinfunction "1_1") (pintype "passive"))
      (node (ref "U2") (pin "1") (pinfunction "OutA_1") (pintype "passive"))
    )
    (net (code "35") (name "Net-(U2-OutB)") (class "Default")
      (node (ref "C28") (pin "2") (pinfunction "2_2") (pintype "passive"))
      (node (ref "R25") (pin "1") (pinfunction "1_1") (pintype "passive"))
      (node (ref "R30") (pin "2") (pinfunction "2_2") (pintype "passive"))
      (node (ref "U2") (pin "7") (pinfunction "OutB_7") (pintype "passive"))
    )
    (net (code "36") (name "Net-(U2-OutC)") (class "Default")
      (node (ref "C29") (pin "1") (pinfunction "1_1") (pintype "passive"))
      (node (ref "R26") (pin "2") (pinfunction "2_2") (pintype "passive"))
      (node (ref "R31") (pin "2") (pinfunction "2_2") (pintype "passive"))
      (node (ref "U2") (pin "8") (pinfunction "OutC_8") (pintype "passive"))
    )
    (net (code "37") (name "Net-(U2-OutD)") (class "Default")
      (node (ref "C23") (pin "1") (pinfunction "1_1") (pintype "passive"))
      (node (ref "R14") (pin "2") (pinfunction "2_2") (pintype "passive"))
      (node (ref "R7") (pin "1") (pinfunction "1_1") (pintype "passive"))
      (node (ref "U2") (pin "14") (pinfunction "OutD_14") (pintype "passive"))
    )
    (net (code "38") (name "Net-(U2-–InA)") (class "Default")
      (node (ref "R17") (pin "1") (pinfunction "1_1") (pintype "passive"))
      (node (ref "U2") (pin "2") (pinfunction "–InA_2") (pintype "passive"))
    )
    (net (code "39") (name "Net-(U2-–InB)") (class "Default")
      (node (ref "R19") (pin "1") (pinfunction "1_1") (pintype "passive"))
      (node (ref "U2") (pin "6") (pinfunction "–InB_6") (pintype "passive"))
    )
    (net (code "40") (name "Net-(U2-–InC)") (class "Default")
      (node (ref "R20") (pin "2") (pinfunction "2_2") (pintype "passive"))
      (node (ref "U2") (pin "9") (pinfunction "–InC_9") (pintype "passive"))
    )
    (net (code "41") (name "Net-(U2-–InD)") (class "Default")
      (node (ref "R18") (pin "2") (pinfunction "2_2") (pintype "passive"))
      (node (ref "U2") (pin "13") (pinfunction "–InD_13") (pintype "passive"))
    )
    (net (code "42") (name "unconnected-(U1-EP-Pad21)") (class "Default")
      (node (ref "U1") (pin "21") (pinfunction "EP_21") (pintype "passive"))
    )
    (net (code "43") (name "unconnected-(U1-NC-Pad6)") (class "Default")
      (node (ref "U1") (pin "6") (pinfunction "NC_6") (pintype "passive"))
    )
    (net (code "44") (name "unconnected-(U1-NC-Pad7)") (class "Default")
      (node (ref "U1") (pin "7") (pinfunction "NC_7") (pintype "passive"))
    )
    (net (code "45") (name "unconnected-(U1-NC-Pad8)") (class "Default")
      (node (ref "U1") (pin "8") (pinfunction "NC_8") (pintype "passive"))
    )
    (net (code "46") (name "unconnected-(U1-NC-Pad9)") (class "Default")
      (node (ref "U1") (pin "9") (pinfunction "NC_9") (pintype "passive"))
    )
    (net (code "47") (name "unconnected-(U1-NC-Pad10)") (class "Default")
      (node (ref "U1") (pin "10") (pinfunction "NC_10") (pintype "passive"))
    )
    (net (code "48") (name "unconnected-(U1-NC-Pad11)") (class "Default")
      (node (ref "U1") (pin "11") (pinfunction "NC_11") (pintype "passive"))
    )
    (net (code "49") (name "unconnected-(U1-NC-Pad12)") (class "Default")
      (node (ref "U1") (pin "12") (pinfunction "NC_12") (pintype "passive"))
    )
    (net (code "50") (name "unconnected-(U1-NC-Pad13)") (class "Default")
      (node (ref "U1") (pin "13") (pinfunction "NC_13") (pintype "passive"))
    )
    (net (code "51") (name "unconnected-(U1-NC-Pad14)") (class "Default")
      (node (ref "U1") (pin "14") (pinfunction "NC_14") (pintype "passive"))
    )
    (net (code "52") (name "unconnected-(U1-NC-Pad15)") (class "Default")
      (node (ref "U1") (pin "15") (pinfunction "NC_15") (pintype "passive"))
    )
  )
)
